# pwr_neg_bipolar.net
KiCad netlist of a schematic drawn in EAGLE
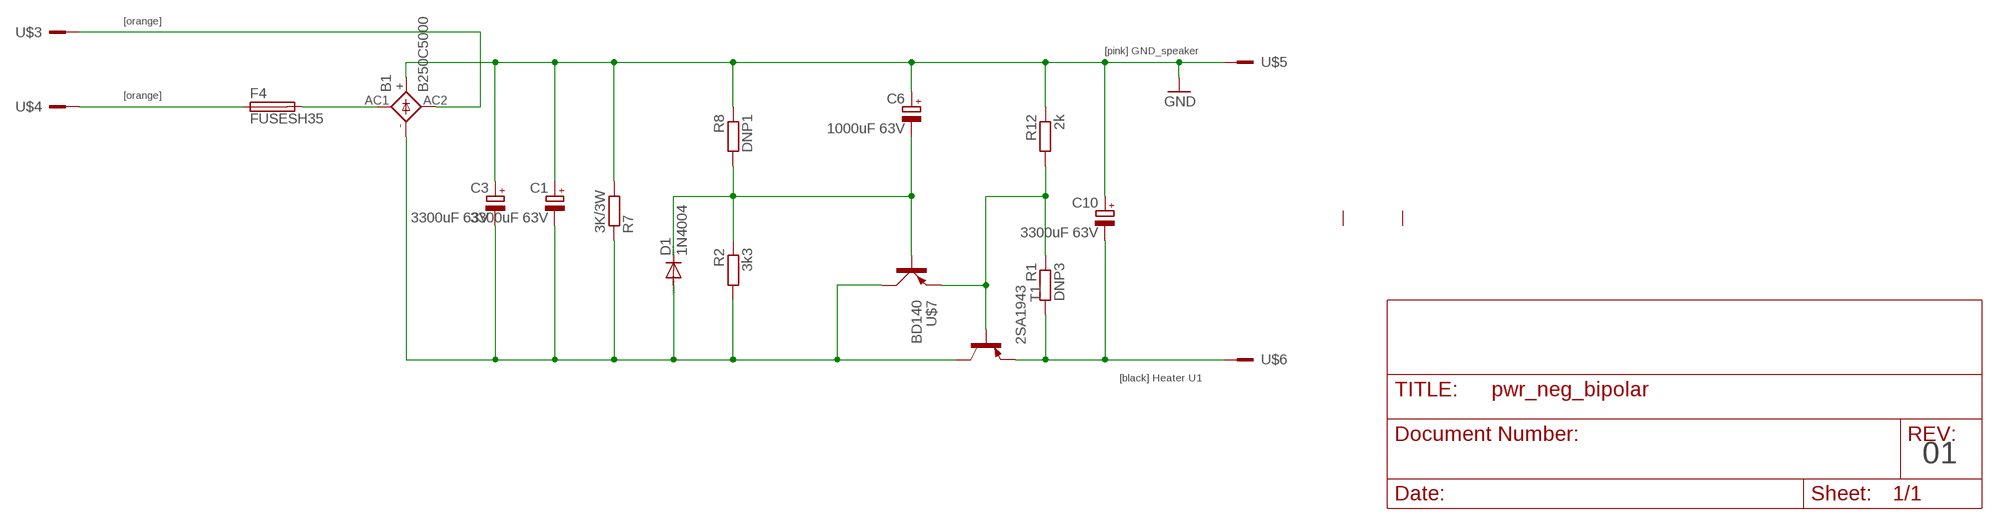
[diagram p0: schematic, sheet 1]

(export (version "E")
  (design (tool "Eeschema 10.0.6"))
  (components
    (comp (ref "B1")
      (value "B250C5000")
      (footprint "eagle-import:DIOTEC_BC5000")
      (libsource (lib "eagle-import") (part "DIOTEC_BC5000"))
    )
    (comp (ref "C1")
      (value "3300uF 63V")
      (footprint "eagle-import:EB20D")
      (libsource (lib "eagle-import") (part "CPOL-EUE10-20"))
    )
    (comp (ref "C3")
      (value "3300uF 63V")
      (footprint "eagle-import:EB20D")
      (libsource (lib "eagle-import") (part "CPOL-EUE10-20"))
    )
    (comp (ref "C6")
      (value "1000uF 63V")
      (footprint "eagle-import:E7,5-16")
      (libsource (lib "eagle-import") (part "CPOL-EUE7.5-16"))
    )
    (comp (ref "C10")
      (value "3300uF 63V")
      (footprint "eagle-import:EB20D")
      (libsource (lib "eagle-import") (part "CPOL-EUE10-20"))
    )
    (comp (ref "D1")
      (value "1N4004")
      (footprint "eagle-import:DO41-10")
      (libsource (lib "eagle-import") (part "1N4004"))
    )
    (comp (ref "F4")
      (value "FUSESH35")
      (footprint "eagle-import:SH25")
      (libsource (lib "eagle-import") (part "FUSESH35"))
    )
    (comp (ref "R1")
      (value "DNP3")
      (footprint "eagle-import:0411_12")
      (libsource (lib "eagle-import") (part "R-EU_0411/12"))
    )
    (comp (ref "R2")
      (value "3k3")
      (footprint "eagle-import:0411_12")
      (libsource (lib "eagle-import") (part "R-EU_0411/12"))
    )
    (comp (ref "R7")
      (value "3K/3W")
      (footprint "eagle-import:0922V")
      (libsource (lib "eagle-import") (part "R-EU_0922V"))
    )
    (comp (ref "R8")
      (value "DNP1")
      (footprint "eagle-import:0411_12")
      (libsource (lib "eagle-import") (part "R-EU_0411/12"))
    )
    (comp (ref "R12")
      (value "2k")
      (footprint "eagle-import:0411_12")
      (libsource (lib "eagle-import") (part "R-EU_0411/12"))
    )
    (comp (ref "T1")
      (value "2SA1943")
      (footprint "eagle-import:TOP3V")
      (libsource (lib "eagle-import") (part "-PNP-TOP3V"))
    )
    (comp (ref "U$1")
      (value "SK456-60-3XM3L")
      (footprint "eagle-import:SK456-60-3XM3L")
      (libsource (lib "eagle-import") (part "SK456-60-3XM3L"))
    )
    (comp (ref "U$2")
      (value "RN_POWER")
      (footprint "eagle-import:RN")
      (libsource (lib "eagle-import") (part "RN_POWER"))
    )
    (comp (ref "U$3")
      (value "M1")
      (footprint "eagle-import:M1_OFFSET")
      (libsource (lib "eagle-import") (part "M1"))
    )
    (comp (ref "U$4")
      (value "M1")
      (footprint "eagle-import:M1_OFFSET")
      (libsource (lib "eagle-import") (part "M1"))
    )
    (comp (ref "U$5")
      (value "M1")
      (footprint "eagle-import:M1_OFFSET")
      (libsource (lib "eagle-import") (part "M1"))
    )
    (comp (ref "U$6")
      (value "M1")
      (footprint "eagle-import:M1_OFFSET")
      (libsource (lib "eagle-import") (part "M1"))
    )
    (comp (ref "U$7")
      (value "BD140")
      (footprint "eagle-import:SOT32")
      (libsource (lib "eagle-import") (part "PNP-POWER_VERT"))
    )
  )
  (nets
    (net (code "1") (name "GND") (class "Default")
      (node (ref "B1") (pin "+") (pinfunction "+_+") (pintype "passive"))
      (node (ref "C1") (pin "+") (pinfunction "+_+") (pintype "passive"))
      (node (ref "C10") (pin "+") (pinfunction "+_+") (pintype "passive"))
      (node (ref "C3") (pin "+") (pinfunction "+_+") (pintype "passive"))
      (node (ref "C6") (pin "+") (pinfunction "+_+") (pintype "passive"))
      (node (ref "R12") (pin "1") (pinfunction "1_1") (pintype "passive"))
      (node (ref "R7") (pin "2") (pinfunction "2_2") (pintype "passive"))
      (node (ref "R8") (pin "1") (pinfunction "1_1") (pintype "passive"))
      (node (ref "U$5") (pin "1") (pinfunction "KL_1") (pintype "passive"))
    )
    (net (code "2") (name "Net-(B1-Pad-)") (class "Default")
      (node (ref "B1") (pin "-") (pinfunction "-_-") (pintype "passive"))
      (node (ref "C1") (pin "-") (pinfunction "-_-") (pintype "passive"))
      (node (ref "C3") (pin "-") (pinfunction "-_-") (pintype "passive"))
      (node (ref "D1") (pin "A") (pinfunction "A_A") (pintype "passive"))
      (node (ref "R2") (pin "2") (pinfunction "2_2") (pintype "passive"))
      (node (ref "R7") (pin "1") (pinfunction "1_1") (pintype "passive"))
      (node (ref "T1") (pin "C") (pinfunction "C_C") (pintype "passive"))
      (node (ref "U$7") (pin "C") (pinfunction "C_C") (pintype "passive"))
    )
    (net (code "3") (name "Net-(B1-PadAC1)") (class "Default")
      (node (ref "B1") (pin "AC1") (pinfunction "AC1_AC1") (pintype "passive"))
      (node (ref "F4") (pin "2") (pinfunction "2_2") (pintype "passive"))
    )
    (net (code "4") (name "Net-(C6-Pad-)") (class "Default")
      (node (ref "C6") (pin "-") (pinfunction "-_-") (pintype "passive"))
      (node (ref "D1") (pin "C") (pinfunction "C_C") (pintype "passive"))
      (node (ref "R2") (pin "1") (pinfunction "1_1") (pintype "passive"))
      (node (ref "R8") (pin "2") (pinfunction "2_2") (pintype "passive"))
      (node (ref "U$7") (pin "B") (pinfunction "B_B") (pintype "passive"))
    )
    (net (code "5") (name "Net-(R1-Pad1)") (class "Default")
      (node (ref "R1") (pin "1") (pinfunction "1_1") (pintype "passive"))
      (node (ref "R12") (pin "2") (pinfunction "2_2") (pintype "passive"))
      (node (ref "T1") (pin "B") (pinfunction "B_B") (pintype "passive"))
      (node (ref "U$7") (pin "E") (pinfunction "E_E") (pintype "passive"))
    )
    (net (code "6") (name "Net-(U$3-KL)") (class "Default")
      (node (ref "B1") (pin "AC2") (pinfunction "AC2_AC2") (pintype "passive"))
      (node (ref "U$3") (pin "1") (pinfunction "KL_1") (pintype "passive"))
    )
    (net (code "7") (name "Net-(U$4-KL)") (class "Default")
      (node (ref "F4") (pin "1") (pinfunction "1_1") (pintype "passive"))
      (node (ref "U$4") (pin "1") (pinfunction "KL_1") (pintype "passive"))
    )
    (net (code "8") (name "Net-(U$6-KL)") (class "Default")
      (node (ref "C10") (pin "-") (pinfunction "-_-") (pintype "passive"))
      (node (ref "R1") (pin "2") (pinfunction "2_2") (pintype "passive"))
      (node (ref "T1") (pin "E") (pinfunction "E_E") (pintype "passive"))
      (node (ref "U$6") (pin "1") (pinfunction "KL_1") (pintype "passive"))
    )
    (net (code "9") (name "unconnected-(U$1-PadP$1)") (class "Default")
      (node (ref "U$1") (pin "P$1") (pinfunction "P$1_P$1") (pintype "no_connect"))
    )
    (net (code "10") (name "unconnected-(U$1-PadP$2)") (class "Default")
      (node (ref "U$1") (pin "P$2") (pinfunction "P$2_P$2") (pintype "no_connect"))
    )
    (net (code "11") (name "unconnected-(U$2-P$1-PadSH@1)") (class "Default")
      (node (ref "U$2") (pin "SH@1") (pinfunction "P$1_SH@1") (pintype "no_connect"))
    )
    (net (code "12") (name "unconnected-(U$2-P$2-PadSH@2)") (class "Default")
      (node (ref "U$2") (pin "SH@2") (pinfunction "P$2_SH@2") (pintype "no_connect"))
    )
    (net (code "13") (name "unconnected-(U$2-P$3-PadSH@3)") (class "Default")
      (node (ref "U$2") (pin "SH@3") (pinfunction "P$3_SH@3") (pintype "no_connect"))
    )
    (net (code "14") (name "unconnected-(U$2-P$4-PadSH@4)") (class "Default")
      (node (ref "U$2") (pin "SH@4") (pinfunction "P$4_SH@4") (pintype "no_connect"))
    )
  )
)
